# Isolated_Supply.net
KiCad netlist of a schematic drawn in Altium Designer
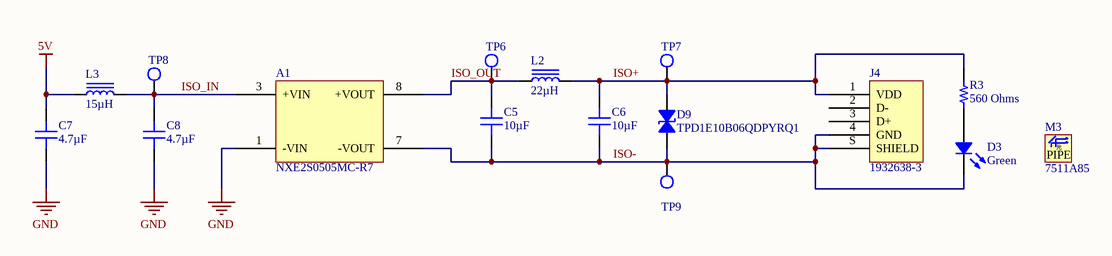
[diagram p0: Isolated Supply.SchDoc]

(export (version "E")
  (design (tool "Eeschema 10.0.6"))
  (components
    (comp (ref "A1")
      (value "NXE2S0505MC-R7")
      (footprint "MURATA NXE")
      (description "DC DC CONVERTER 5V 2W")
      (fields
        (field (name "PART NUMBER") "NXE2S0505MC-R7")
        (field (name "MANUFACTURER") "Murata Power Solutions Inc.")
      )
      (libsource (lib "Celestial Altium Library - altium_library") (part "MURATA NXE"))
    )
    (comp (ref "C5")
      (value "10µF")
      (footprint "CAP 1206_3216 - 1.8MM")
      (description "CAP CER 10UF 16V X7R 1206")
      (fields
        (field (name "PART NUMBER") "CL31B106MOHNNNE")
        (field (name "MANUFACTURER") "Samsung Electro-Mechanics")
      )
      (libsource (lib "Celestial Altium Library - altium_library") (part "Capacitor"))
    )
    (comp (ref "C6")
      (value "10µF")
      (footprint "CAP 1206_3216 - 1.8MM")
      (description "CAP CER 10UF 16V X7R 1206")
      (fields
        (field (name "PART NUMBER") "CL31B106MOHNNNE")
        (field (name "MANUFACTURER") "Samsung Electro-Mechanics")
      )
      (libsource (lib "Celestial Altium Library - altium_library") (part "Capacitor"))
    )
    (comp (ref "C7")
      (value "4.7µF")
      (footprint "CAP 1206_3216 - 1.8MM")
      (description "CAP CER 4.7UF 16V X7R 1206")
      (fields
        (field (name "PART NUMBER") "CL31B475KOHNNNE")
        (field (name "MANUFACTURER") "Samsung Electro-Mechanics")
      )
      (libsource (lib "Celestial Altium Library - altium_library") (part "Capacitor"))
    )
    (comp (ref "C8")
      (value "4.7µF")
      (footprint "CAP 1206_3216 - 1.8MM")
      (description "CAP CER 4.7UF 16V X7R 1206")
      (fields
        (field (name "PART NUMBER") "CL31B475KOHNNNE")
        (field (name "MANUFACTURER") "Samsung Electro-Mechanics")
      )
      (libsource (lib "Celestial Altium Library - altium_library") (part "Capacitor"))
    )
    (comp (ref "D3")
      (value "Green")
      (footprint "LED 0805_2012 GREEN")
      (description "LED GREEN CLEAR SMD")
      (fields (field (name "PART NUMBER") "LTST-C170GKT") (field (name "MANUFACTURER") "Lite-On Inc."))
      (libsource (lib "Celestial Altium Library - altium_library") (part "LED"))
    )
    (comp (ref "D9")
      (value "TPD1E10B06QDPYRQ1")
      (footprint "0402")
      (description "TVS DIODE 5.5V 14V 2X1SON")
      (fields (field (name "MANUFACTURER") "Texas Instruments"))
      (libsource (lib "Celestial Altium Library - altium_library") (part "Diode TVS"))
    )
    (comp (ref "J4")
      (value "1932638-3")
      (footprint "TE 1932638-3 USB2.0A")
      (description "CONN RCPT USB2.0 TYPEA 4P SMD RA")
      (fields (field (name "MANUFACTURER") "TE Connectivity AMP Connectors"))
      (libsource (lib "Celestial Altium Library - altium_library") (part "TE 1932638-3"))
    )
    (comp (ref "L2")
      (value "22µH")
      (footprint "TDK VLCF4024-2")
      (description "FIXED IND 22UH 650MA 332 MOHM")
      (fields
        (field (name "PART NUMBER") "VLCF4024T-220MR65-2")
        (field (name "MANUFACTURER") "TDK Corporation")
      )
      (libsource (lib "Celestial Altium Library - altium_library") (part "Inductor"))
    )
    (comp (ref "L3")
      (value "15µH")
      (footprint "TDK VLCF4028-2")
      (description "FIXED IND 15UH 880MA 170 MOHM")
      (fields
        (field (name "PART NUMBER") "VLCF4028T-150MR88-2")
        (field (name "MANUFACTURER") "TDK Corporation")
      )
      (libsource (lib "Celestial Altium Library - altium_library") (part "Inductor"))
    )
    (comp (ref "M3")
      (value "7511A85")
      (footprint "VCC 7511A85")
      (description "LIGHT PIPE RIGHT ANG SINGLE POS")
      (fields (field (name "MANUFACTURER") "Visual Communications Company - VCC"))
      (libsource (lib "Celestial Altium Library - altium_library") (part "Light Pipe"))
    )
    (comp (ref "R3")
      (value "560 Ohms")
      (footprint "RES 0603_1608")
      (description "RES SMD 560 OHM 5% 1/4W 0603")
      (fields
        (field (name "PART NUMBER") "ERJ-PA3J561V")
        (field (name "MANUFACTURER") "Panasonic Electronic Components")
      )
      (libsource (lib "Celestial Altium Library - altium_library") (part "Resistor"))
    )
    (comp (ref "TP6")
      (value "Test Point")
      (footprint "TestPoint-1.5mm")
      (libsource (lib "CelestialUseful") (part "Test Point"))
    )
    (comp (ref "TP7")
      (value "Test Point")
      (footprint "TestPoint-1.5mm")
      (libsource (lib "CelestialUseful") (part "Test Point"))
    )
    (comp (ref "TP8")
      (value "Test Point")
      (footprint "TestPoint-1.5mm")
      (libsource (lib "CelestialUseful") (part "Test Point"))
    )
    (comp (ref "TP9")
      (value "Test Point")
      (footprint "TestPoint-1.5mm")
      (libsource (lib "CelestialUseful") (part "Test Point"))
    )
  )
  (nets
    (net (code "1") (name "/ISO+") (class "Default")
      (node (ref "C6") (pin "1") (pinfunction "1_1") (pintype "passive"))
      (node (ref "D9") (pin "2") (pinfunction "2_2") (pintype "passive"))
      (node (ref "J4") (pin "1") (pinfunction "VDD_1") (pintype "passive"))
      (node (ref "L2") (pin "2") (pinfunction "2_2") (pintype "passive"))
      (node (ref "R3") (pin "1") (pinfunction "1_1") (pintype "passive"))
      (node (ref "TP7") (pin "1") (pinfunction "TP_1") (pintype "passive"))
    )
    (net (code "2") (name "/ISO-") (class "Default")
      (node (ref "A1") (pin "7") (pinfunction "-VOUT_7") (pintype "passive"))
      (node (ref "C5") (pin "2") (pinfunction "2_2") (pintype "passive"))
      (node (ref "C6") (pin "2") (pinfunction "2_2") (pintype "passive"))
      (node (ref "D3") (pin "2") (pinfunction "2_2") (pintype "passive"))
      (node (ref "D9") (pin "1") (pinfunction "1_1") (pintype "passive"))
      (node (ref "J4") (pin "4") (pinfunction "GND_4") (pintype "passive"))
      (node (ref "J4") (pin "S") (pinfunction "SHIELD_S") (pintype "passive"))
      (node (ref "TP9") (pin "1") (pinfunction "TP_1") (pintype "passive"))
    )
    (net (code "3") (name "/ISO_IN") (class "Default")
      (node (ref "A1") (pin "3") (pinfunction "+VIN_3") (pintype "passive"))
      (node (ref "C8") (pin "1") (pinfunction "1_1") (pintype "passive"))
      (node (ref "L3") (pin "2") (pinfunction "2_2") (pintype "passive"))
      (node (ref "TP8") (pin "1") (pinfunction "TP_1") (pintype "passive"))
    )
    (net (code "4") (name "/ISO_OUT") (class "Default")
      (node (ref "A1") (pin "8") (pinfunction "+VOUT_8") (pintype "passive"))
      (node (ref "C5") (pin "1") (pinfunction "1_1") (pintype "passive"))
      (node (ref "L2") (pin "1") (pinfunction "1_1") (pintype "passive"))
      (node (ref "TP6") (pin "1") (pinfunction "TP_1") (pintype "passive"))
    )
    (net (code "5") (name "5V") (class "Default")
      (node (ref "C7") (pin "1") (pinfunction "1_1") (pintype "passive"))
      (node (ref "L3") (pin "1") (pinfunction "1_1") (pintype "passive"))
    )
    (net (code "6") (name "GND") (class "Default")
      (node (ref "A1") (pin "1") (pinfunction "-VIN_1") (pintype "passive"))
      (node (ref "C7") (pin "2") (pinfunction "2_2") (pintype "passive"))
      (node (ref "C8") (pin "2") (pinfunction "2_2") (pintype "passive"))
    )
    (net (code "7") (name "Net-(D3-Pad1)") (class "Default")
      (node (ref "D3") (pin "1") (pinfunction "1_1") (pintype "passive"))
      (node (ref "R3") (pin "2") (pinfunction "2_2") (pintype "passive"))
    )
    (net (code "8") (name "unconnected-(J4-D+-Pad3)") (class "Default")
      (node (ref "J4") (pin "3") (pinfunction "D+_3") (pintype "passive"))
    )
    (net (code "9") (name "unconnected-(J4-D--Pad2)") (class "Default")
      (node (ref "J4") (pin "2") (pinfunction "D-_2") (pintype "passive"))
    )
  )
)
